# Output.net
KiCad netlist of a schematic drawn in Altium Designer
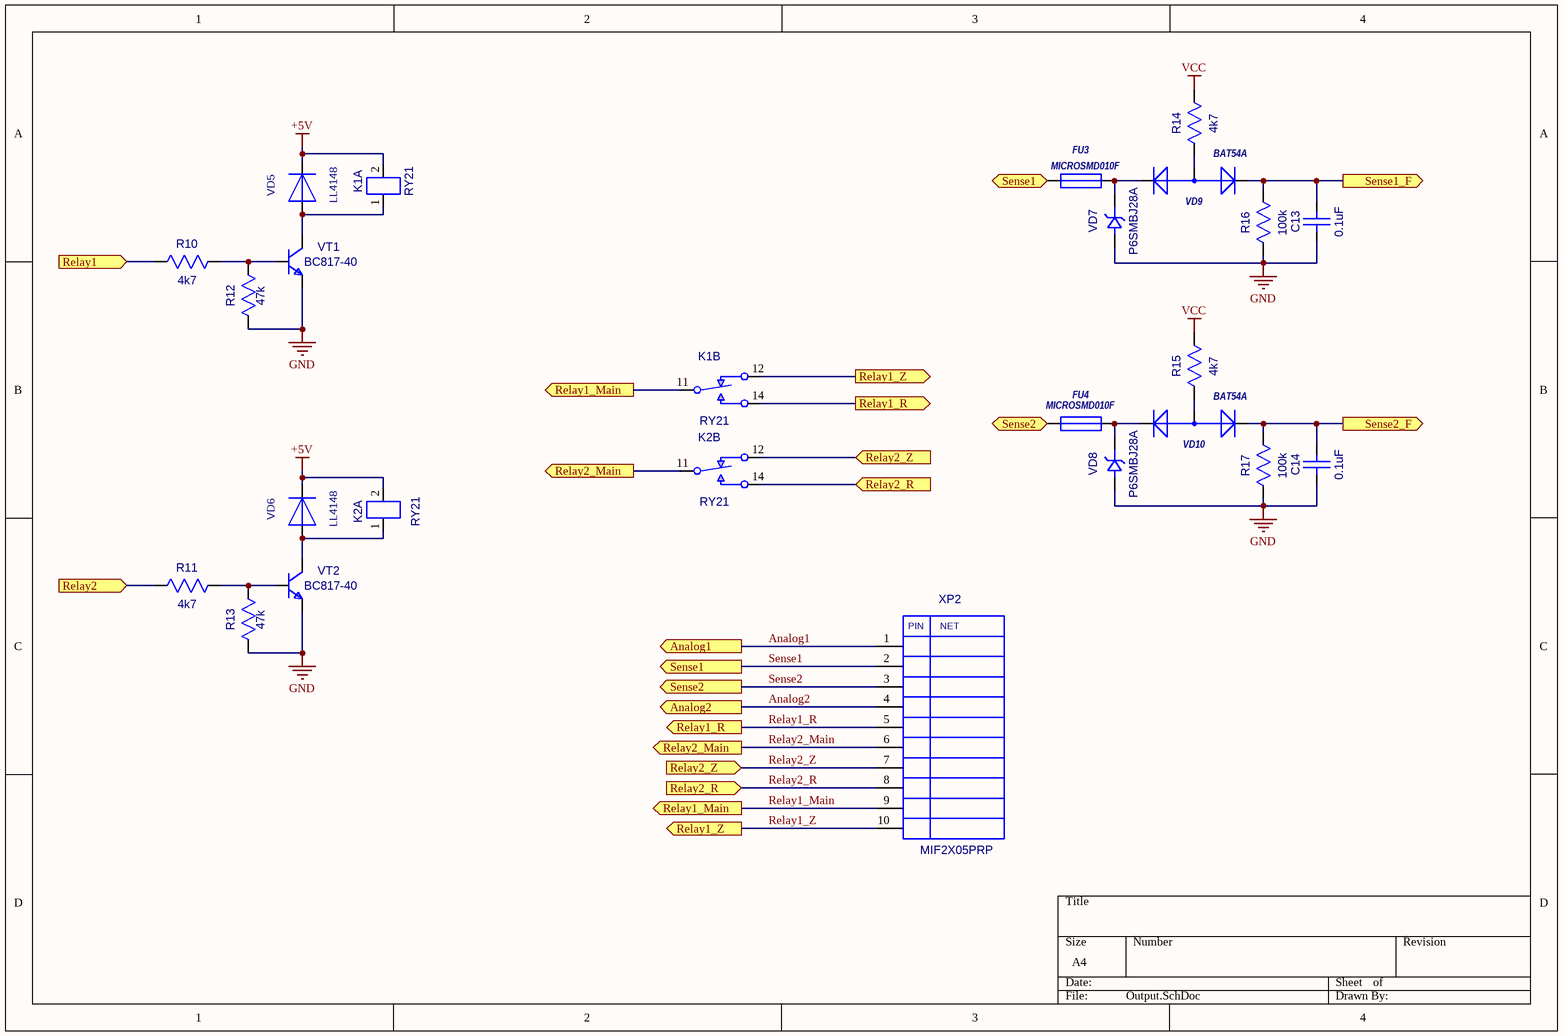
[diagram p0: Output.SchDoc]

(export (version "E")
  (design (tool "Eeschema 10.0.6"))
  (components
    (comp (ref "C13")
      (value "0.1uF")
      (footprint "CC0603-3M")
      (description "CC0603")
      (libsource (lib "gprs_modem") (part "CC0603"))
    )
    (comp (ref "C14")
      (value "0.1uF")
      (footprint "CC0603-3M")
      (description "CC0603")
      (libsource (lib "gprs_modem") (part "CC0603"))
    )
    (comp (ref "FU3")
      (value "MICROSMD010F")
      (footprint "RC1210")
      (description "MICROSMD")
      (libsource (lib "gprs_modem") (part "MICROSMD"))
    )
    (comp (ref "FU4")
      (value "MICROSMD010F")
      (footprint "RC1210")
      (description "MICROSMD")
      (libsource (lib "gprs_modem") (part "MICROSMD"))
    )
    (comp (ref "K1")
      (value "RY21")
      (footprint "RY21_RY21(Primary)")
      (libsource (lib "shlagbaum") (part "RY21"))
    )
    (comp (ref "K2")
      (value "RY21")
      (footprint "RY21_RY21(Primary)")
      (libsource (lib "shlagbaum") (part "RY21"))
    )
    (comp (ref "R10")
      (value "4k7")
      (footprint "RC0603-3M")
      (description "RC0603")
      (libsource (lib "gprs_modem") (part "RC0603"))
    )
    (comp (ref "R11")
      (value "4k7")
      (footprint "RC0603-3M")
      (description "RC0603")
      (libsource (lib "gprs_modem") (part "RC0603"))
    )
    (comp (ref "R12")
      (value "47k")
      (footprint "RC0603-3M")
      (description "RC0603")
      (libsource (lib "gprs_modem") (part "RC0603"))
    )
    (comp (ref "R13")
      (value "47k")
      (footprint "RC0603-3M")
      (description "RC0603")
      (libsource (lib "gprs_modem") (part "RC0603"))
    )
    (comp (ref "R14")
      (value "4k7")
      (footprint "RC0603-3M")
      (description "RC0603")
      (libsource (lib "gprs_modem") (part "RC0603"))
    )
    (comp (ref "R15")
      (value "4k7")
      (footprint "RC0603-3M")
      (description "RC0603")
      (libsource (lib "gprs_modem") (part "RC0603"))
    )
    (comp (ref "R16")
      (value "100k")
      (footprint "RC0603-3M")
      (description "RC0603")
      (libsource (lib "gprs_modem") (part "RC0603"))
    )
    (comp (ref "R17")
      (value "100k")
      (footprint "RC0603-3M")
      (description "RC0603")
      (libsource (lib "gprs_modem") (part "RC0603"))
    )
    (comp (ref "VD5") (value "LL4148") (footprint "SOD-80") (libsource (lib "gprs_modem_2") (part "LL4148")))
    (comp (ref "VD6") (value "LL4148") (footprint "SOD-80") (libsource (lib "gprs_modem_2") (part "LL4148")))
    (comp (ref "VD7")
      (value "P6SMBJ28A")
      (footprint "SMB")
      (description "SMBJ")
      (libsource (lib "gprs_modem") (part "SMBJ"))
    )
    (comp (ref "VD8")
      (value "P6SMBJ28A")
      (footprint "SMB")
      (description "SMBJ")
      (libsource (lib "gprs_modem") (part "SMBJ"))
    )
    (comp (ref "VD9")
      (value "BAT54A")
      (footprint "SOT-23(123)")
      (description "1.0 Ampere General Purpose Rectifier")
      (libsource (lib "gprs_modem") (part "BAT54A"))
    )
    (comp (ref "VD10")
      (value "BAT54A")
      (footprint "SOT-23(123)")
      (description "1.0 Ampere General Purpose Rectifier")
      (libsource (lib "gprs_modem") (part "BAT54A"))
    )
    (comp (ref "VT1")
      (value "BC817-40")
      (footprint "SOT-23(123)")
      (description "BC846BLT1")
      (libsource (lib "gprs_modem_2") (part "BC846BLT1"))
    )
    (comp (ref "VT2")
      (value "BC817-40")
      (footprint "SOT-23(123)")
      (description "BC846BLT1")
      (libsource (lib "gprs_modem_2") (part "BC846BLT1"))
    )
    (comp (ref "XP2")
      (value "MIF2X05PRP")
      (footprint "MIF2X05PRP")
      (libsource (lib "shlagbaum") (part "MIF2X05PRP"))
    )
  )
  (nets
    (net (code "1") (name "+5V") (class "Default")
      (node (ref "K1") (pin "2") (pinfunction "C2_2") (pintype "passive"))
      (node (ref "K2") (pin "2") (pinfunction "C2_2") (pintype "passive"))
      (node (ref "VD5") (pin "2") (pinfunction "+_2") (pintype "passive"))
      (node (ref "VD6") (pin "2") (pinfunction "+_2") (pintype "passive"))
    )
    (net (code "2") (name "/Analog1") (class "Default")
      (node (ref "XP2") (pin "1") (pinfunction "1_1") (pintype "passive"))
    )
    (net (code "3") (name "/Analog2") (class "Default")
      (node (ref "XP2") (pin "4") (pinfunction "4_4") (pintype "passive"))
    )
    (net (code "4") (name "/Relay1") (class "Default")
      (node (ref "R10") (pin "1") (pinfunction "A_1") (pintype "passive"))
    )
    (net (code "5") (name "/Relay1_Main") (class "Default")
      (node (ref "K1") (pin "11") (pinfunction "C1_11") (pintype "passive"))
      (node (ref "XP2") (pin "9") (pinfunction "9_9") (pintype "passive"))
    )
    (net (code "6") (name "/Relay1_R") (class "Default")
      (node (ref "K1") (pin "14") (pinfunction "C2_14") (pintype "passive"))
      (node (ref "XP2") (pin "5") (pinfunction "5_5") (pintype "passive"))
    )
    (net (code "7") (name "/Relay1_Z") (class "Default")
      (node (ref "K1") (pin "12") (pinfunction "C3_12") (pintype "passive"))
      (node (ref "XP2") (pin "10") (pinfunction "10_10") (pintype "passive"))
    )
    (net (code "8") (name "/Relay2") (class "Default")
      (node (ref "R11") (pin "1") (pinfunction "A_1") (pintype "passive"))
    )
    (net (code "9") (name "/Relay2_Main") (class "Default")
      (node (ref "K2") (pin "11") (pinfunction "C1_11") (pintype "passive"))
      (node (ref "XP2") (pin "6") (pinfunction "6_6") (pintype "passive"))
    )
    (net (code "10") (name "/Relay2_R") (class "Default")
      (node (ref "K2") (pin "14") (pinfunction "C2_14") (pintype "passive"))
      (node (ref "XP2") (pin "8") (pinfunction "8_8") (pintype "passive"))
    )
    (net (code "11") (name "/Relay2_Z") (class "Default")
      (node (ref "K2") (pin "12") (pinfunction "C3_12") (pintype "passive"))
      (node (ref "XP2") (pin "7") (pinfunction "7_7") (pintype "passive"))
    )
    (net (code "12") (name "/Sense1") (class "Default")
      (node (ref "FU3") (pin "1") (pintype "passive"))
      (node (ref "XP2") (pin "2") (pinfunction "2_2") (pintype "passive"))
    )
    (net (code "13") (name "/Sense1_F") (class "Default")
      (node (ref "C13") (pin "2") (pinfunction "B_2") (pintype "passive"))
      (node (ref "R16") (pin "2") (pinfunction "B_2") (pintype "passive"))
      (node (ref "VD9") (pin "1") (pinfunction "K_1") (pintype "passive"))
    )
    (net (code "14") (name "/Sense2") (class "Default")
      (node (ref "FU4") (pin "1") (pintype "passive"))
      (node (ref "XP2") (pin "3") (pinfunction "3_3") (pintype "passive"))
    )
    (net (code "15") (name "/Sense2_F") (class "Default")
      (node (ref "C14") (pin "2") (pinfunction "B_2") (pintype "passive"))
      (node (ref "R17") (pin "2") (pinfunction "B_2") (pintype "passive"))
      (node (ref "VD10") (pin "1") (pinfunction "K_1") (pintype "passive"))
    )
    (net (code "16") (name "GND") (class "Default")
      (node (ref "C13") (pin "1") (pinfunction "A_1") (pintype "passive"))
      (node (ref "C14") (pin "1") (pinfunction "A_1") (pintype "passive"))
      (node (ref "R12") (pin "1") (pinfunction "A_1") (pintype "passive"))
      (node (ref "R13") (pin "1") (pinfunction "A_1") (pintype "passive"))
      (node (ref "R16") (pin "1") (pinfunction "A_1") (pintype "passive"))
      (node (ref "R17") (pin "1") (pinfunction "A_1") (pintype "passive"))
      (node (ref "VD7") (pin "1") (pinfunction "A_1") (pintype "passive"))
      (node (ref "VD8") (pin "1") (pinfunction "A_1") (pintype "passive"))
      (node (ref "VT1") (pin "2") (pinfunction "E_2") (pintype "passive"))
      (node (ref "VT2") (pin "2") (pinfunction "E_2") (pintype "passive"))
    )
    (net (code "17") (name "Net-(K1A-L1)") (class "Default")
      (node (ref "K1") (pin "1") (pinfunction "L1_1") (pintype "passive"))
      (node (ref "VD5") (pin "1") (pinfunction "-_1") (pintype "passive"))
      (node (ref "VT1") (pin "3") (pinfunction "C_3") (pintype "passive"))
    )
    (net (code "18") (name "Net-(K2A-L1)") (class "Default")
      (node (ref "K2") (pin "1") (pinfunction "L1_1") (pintype "passive"))
      (node (ref "VD6") (pin "1") (pinfunction "-_1") (pintype "passive"))
      (node (ref "VT2") (pin "3") (pinfunction "C_3") (pintype "passive"))
    )
    (net (code "19") (name "Net-(R10-B)") (class "Default")
      (node (ref "R10") (pin "2") (pinfunction "B_2") (pintype "passive"))
      (node (ref "R12") (pin "2") (pinfunction "B_2") (pintype "passive"))
      (node (ref "VT1") (pin "1") (pinfunction "B_1") (pintype "passive"))
    )
    (net (code "20") (name "Net-(R11-B)") (class "Default")
      (node (ref "R11") (pin "2") (pinfunction "B_2") (pintype "passive"))
      (node (ref "R13") (pin "2") (pinfunction "B_2") (pintype "passive"))
      (node (ref "VT2") (pin "1") (pinfunction "B_1") (pintype "passive"))
    )
    (net (code "21") (name "Net-(R14-A)") (class "Default")
      (node (ref "R14") (pin "1") (pinfunction "A_1") (pintype "passive"))
      (node (ref "VD9") (pin "3") (pinfunction "A_3") (pintype "passive"))
    )
    (net (code "22") (name "Net-(R15-A)") (class "Default")
      (node (ref "R15") (pin "1") (pinfunction "A_1") (pintype "passive"))
      (node (ref "VD10") (pin "3") (pinfunction "A_3") (pintype "passive"))
    )
    (net (code "23") (name "Net-(VD7-K)") (class "Default")
      (node (ref "FU3") (pin "2") (pintype "passive"))
      (node (ref "VD7") (pin "2") (pinfunction "K_2") (pintype "passive"))
      (node (ref "VD9") (pin "2") (pinfunction "K_2") (pintype "passive"))
    )
    (net (code "24") (name "Net-(VD8-K)") (class "Default")
      (node (ref "FU4") (pin "2") (pintype "passive"))
      (node (ref "VD10") (pin "2") (pinfunction "K_2") (pintype "passive"))
      (node (ref "VD8") (pin "2") (pinfunction "K_2") (pintype "passive"))
    )
    (net (code "25") (name "VCC") (class "Default")
      (node (ref "R14") (pin "2") (pinfunction "B_2") (pintype "passive"))
      (node (ref "R15") (pin "2") (pinfunction "B_2") (pintype "passive"))
    )
  )
)
